# DCDC.net
KiCad netlist of a schematic drawn in Altium Designer
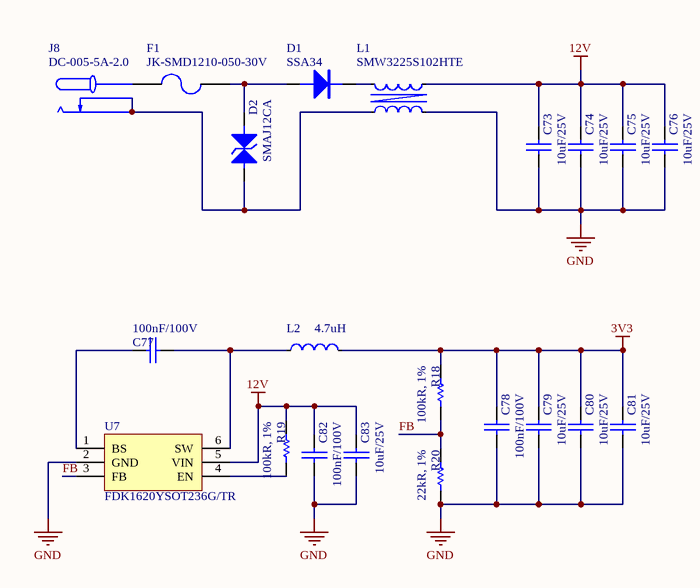
[diagram p0: DCDC.SchDoc]

(export (version "E")
  (design (tool "Eeschema 10.0.6"))
  (components
    (comp (ref "C73")
      (value "10uF/25V")
      (footprint "0603C")
      (description "CC0603MRX5R8BB106")
      (libsource (lib "MyLib") (part "CAP"))
    )
    (comp (ref "C74")
      (value "10uF/25V")
      (footprint "0603C")
      (description "CC0603MRX5R8BB106")
      (libsource (lib "MyLib") (part "CAP"))
    )
    (comp (ref "C75")
      (value "10uF/25V")
      (footprint "0603C")
      (description "CC0603MRX5R8BB106")
      (libsource (lib "MyLib") (part "CAP"))
    )
    (comp (ref "C76")
      (value "10uF/25V")
      (footprint "0603C")
      (description "CC0603MRX5R8BB106")
      (libsource (lib "MyLib") (part "CAP"))
    )
    (comp (ref "C77")
      (value "100nF/100V")
      (footprint "0603C")
      (description "CC0603KRX7R9BB104")
      (libsource (lib "MyLib") (part "CAP"))
    )
    (comp (ref "C78")
      (value "100nF/100V")
      (footprint "0603C")
      (description "CC0603KRX7R9BB104")
      (libsource (lib "MyLib") (part "CAP"))
    )
    (comp (ref "C79")
      (value "10uF/25V")
      (footprint "0603C")
      (description "CC0603MRX5R8BB106")
      (libsource (lib "MyLib") (part "CAP"))
    )
    (comp (ref "C80")
      (value "10uF/25V")
      (footprint "0603C")
      (description "CC0603MRX5R8BB106")
      (libsource (lib "MyLib") (part "CAP"))
    )
    (comp (ref "C81")
      (value "10uF/25V")
      (footprint "0603C")
      (description "CC0603MRX5R8BB106")
      (libsource (lib "MyLib") (part "CAP"))
    )
    (comp (ref "C82")
      (value "100nF/100V")
      (footprint "0603C")
      (description "CC0603KRX7R9BB104")
      (libsource (lib "MyLib") (part "CAP"))
    )
    (comp (ref "C83")
      (value "10uF/25V")
      (footprint "0603C")
      (description "CC0603MRX5R8BB106")
      (libsource (lib "MyLib") (part "CAP"))
    )
    (comp (ref "D1")
      (value "SSA34")
      (footprint "SMA/DO-214AC")
      (description "普通二极管")
      (libsource (lib "MyLib") (part "DIODE"))
    )
    (comp (ref "D2") (value "SMAJ12CA") (footprint "SMA/DO-214AC") (libsource (lib "MyLib") (part "TVS")))
    (comp (ref "F1")
      (value "JK-SMD1210-050-30V")
      (footprint "FUSE-1210")
      (libsource (lib "MyLib") (part "FUSE"))
    )
    (comp (ref "J8")
      (value "DC-005-5A-2.0")
      (footprint "DC-IN-TH_DC-005-5A-2.0")
      (fields (field (name "MANUFACTURER") "XKB Connection(中国星坤)"))
      (libsource (lib "CustomizedLib") (part "DC-005-5A-2.0"))
    )
    (comp (ref "L1")
      (value "SMW3225S102HTE")
      (footprint "INDDFN4_320X250X240L65X80N")
      (description "1.2A")
      (fields (field (name "MANUFACTURER") "cjiang(长江微电)") (field (name "MANUFACTURER PART") "FXL0530-100-M"))
      (libsource (lib "CustomizedLib") (part "SMW3225S102HTE"))
    )
    (comp (ref "L2")
      (value "4.7uH")
      (footprint "L0420")
      (description "FXL0420-4R7-M")
      (fields (field (name "MANUFACTURER") "cjiang(长江微电)") (field (name "MANUFACTURER PART") "FXL0530-100-M"))
      (libsource (lib "CustomizedLib") (part "FXL0420-4R7-M"))
    )
    (comp (ref "R18")
      (value "100kR, 1%")
      (footprint "0603R")
      (description "RC0603FR-07100KL")
      (libsource (lib "MyLib") (part "RES"))
    )
    (comp (ref "R19")
      (value "100kR, 1%")
      (footprint "0603R")
      (description "RC0603FR-07100KL")
      (libsource (lib "MyLib") (part "RES"))
    )
    (comp (ref "R20")
      (value "22kR, 1%")
      (footprint "0603R")
      (description "RC0603FR-0722KL")
      (libsource (lib "MyLib") (part "RES"))
    )
    (comp (ref "U7")
      (value "FDK1620YSOT236G/TR")
      (footprint "SOT23-6")
      (description "DC/DC Converter")
      (libsource (lib "CustomizedLib") (part "FDK1620YSOT236G/TR"))
    )
  )
  (nets
    (net (code "1") (name "/FB") (class "Default")
      (node (ref "R18") (pin "2") (pinfunction "2_2") (pintype "passive"))
      (node (ref "R20") (pin "1") (pinfunction "1_1") (pintype "passive"))
      (node (ref "U7") (pin "3") (pinfunction "FB_3") (pintype "passive"))
    )
    (net (code "2") (name "3V3") (class "Default")
      (node (ref "C78") (pin "2") (pinfunction "2_2") (pintype "passive"))
      (node (ref "C79") (pin "2") (pinfunction "2_2") (pintype "passive"))
      (node (ref "C80") (pin "2") (pinfunction "2_2") (pintype "passive"))
      (node (ref "C81") (pin "2") (pinfunction "2_2") (pintype "passive"))
      (node (ref "L2") (pin "2") (pinfunction "2_2") (pintype "passive"))
      (node (ref "R18") (pin "1") (pinfunction "1_1") (pintype "passive"))
    )
    (net (code "3") (name "12V") (class "Default")
      (node (ref "C73") (pin "2") (pinfunction "2_2") (pintype "passive"))
      (node (ref "C74") (pin "2") (pinfunction "2_2") (pintype "passive"))
      (node (ref "C75") (pin "2") (pinfunction "2_2") (pintype "passive"))
      (node (ref "C76") (pin "2") (pinfunction "2_2") (pintype "passive"))
      (node (ref "C82") (pin "2") (pinfunction "2_2") (pintype "passive"))
      (node (ref "C83") (pin "2") (pinfunction "2_2") (pintype "passive"))
      (node (ref "L1") (pin "4") (pinfunction "4_4") (pintype "passive"))
      (node (ref "R19") (pin "1") (pinfunction "1_1") (pintype "passive"))
      (node (ref "U7") (pin "5") (pinfunction "VIN_5") (pintype "passive"))
    )
    (net (code "4") (name "GND") (class "Default")
      (node (ref "C73") (pin "1") (pinfunction "1_1") (pintype "passive"))
      (node (ref "C74") (pin "1") (pinfunction "1_1") (pintype "passive"))
      (node (ref "C75") (pin "1") (pinfunction "1_1") (pintype "passive"))
      (node (ref "C76") (pin "1") (pinfunction "1_1") (pintype "passive"))
      (node (ref "C78") (pin "1") (pinfunction "1_1") (pintype "passive"))
      (node (ref "C79") (pin "1") (pinfunction "1_1") (pintype "passive"))
      (node (ref "C80") (pin "1") (pinfunction "1_1") (pintype "passive"))
      (node (ref "C81") (pin "1") (pinfunction "1_1") (pintype "passive"))
      (node (ref "C82") (pin "1") (pinfunction "1_1") (pintype "passive"))
      (node (ref "C83") (pin "1") (pinfunction "1_1") (pintype "passive"))
      (node (ref "L1") (pin "3") (pinfunction "3_3") (pintype "passive"))
      (node (ref "R20") (pin "2") (pinfunction "2_2") (pintype "passive"))
      (node (ref "U7") (pin "2") (pinfunction "GND_2") (pintype "passive"))
    )
    (net (code "5") (name "Net-(D1-PadA)") (class "Default")
      (node (ref "D1") (pin "A") (pinfunction "A_A") (pintype "passive"))
      (node (ref "D2") (pin "K") (pinfunction "K_K") (pintype "passive"))
      (node (ref "F1") (pin "2") (pinfunction "2_2") (pintype "passive"))
    )
    (net (code "6") (name "Net-(D1-PadK)") (class "Default")
      (node (ref "D1") (pin "K") (pinfunction "K_K") (pintype "passive"))
      (node (ref "L1") (pin "1") (pinfunction "1_1") (pintype "passive"))
    )
    (net (code "7") (name "Net-(D2-PadA)") (class "Default")
      (node (ref "D2") (pin "A") (pinfunction "A_A") (pintype "passive"))
      (node (ref "J8") (pin "2") (pinfunction "2_2") (pintype "passive"))
      (node (ref "J8") (pin "3") (pinfunction "3_3") (pintype "passive"))
      (node (ref "L1") (pin "2") (pinfunction "2_2") (pintype "passive"))
    )
    (net (code "8") (name "Net-(F1-Pad1)") (class "Default")
      (node (ref "F1") (pin "1") (pinfunction "1_1") (pintype "passive"))
      (node (ref "J8") (pin "1") (pinfunction "1_1") (pintype "passive"))
    )
    (net (code "9") (name "Net-(U7-BS)") (class "Default")
      (node (ref "C77") (pin "2") (pinfunction "2_2") (pintype "passive"))
      (node (ref "U7") (pin "1") (pinfunction "BS_1") (pintype "passive"))
    )
    (net (code "10") (name "Net-(U7-EN)") (class "Default")
      (node (ref "R19") (pin "2") (pinfunction "2_2") (pintype "passive"))
      (node (ref "U7") (pin "4") (pinfunction "EN_4") (pintype "passive"))
    )
    (net (code "11") (name "Net-(U7-SW)") (class "Default")
      (node (ref "C77") (pin "1") (pinfunction "1_1") (pintype "passive"))
      (node (ref "L2") (pin "1") (pinfunction "1_1") (pintype "passive"))
      (node (ref "U7") (pin "6") (pinfunction "SW_6") (pintype "passive"))
    )
  )
)
